# FT232RL.net
KiCad netlist of a schematic drawn in Altium Designer
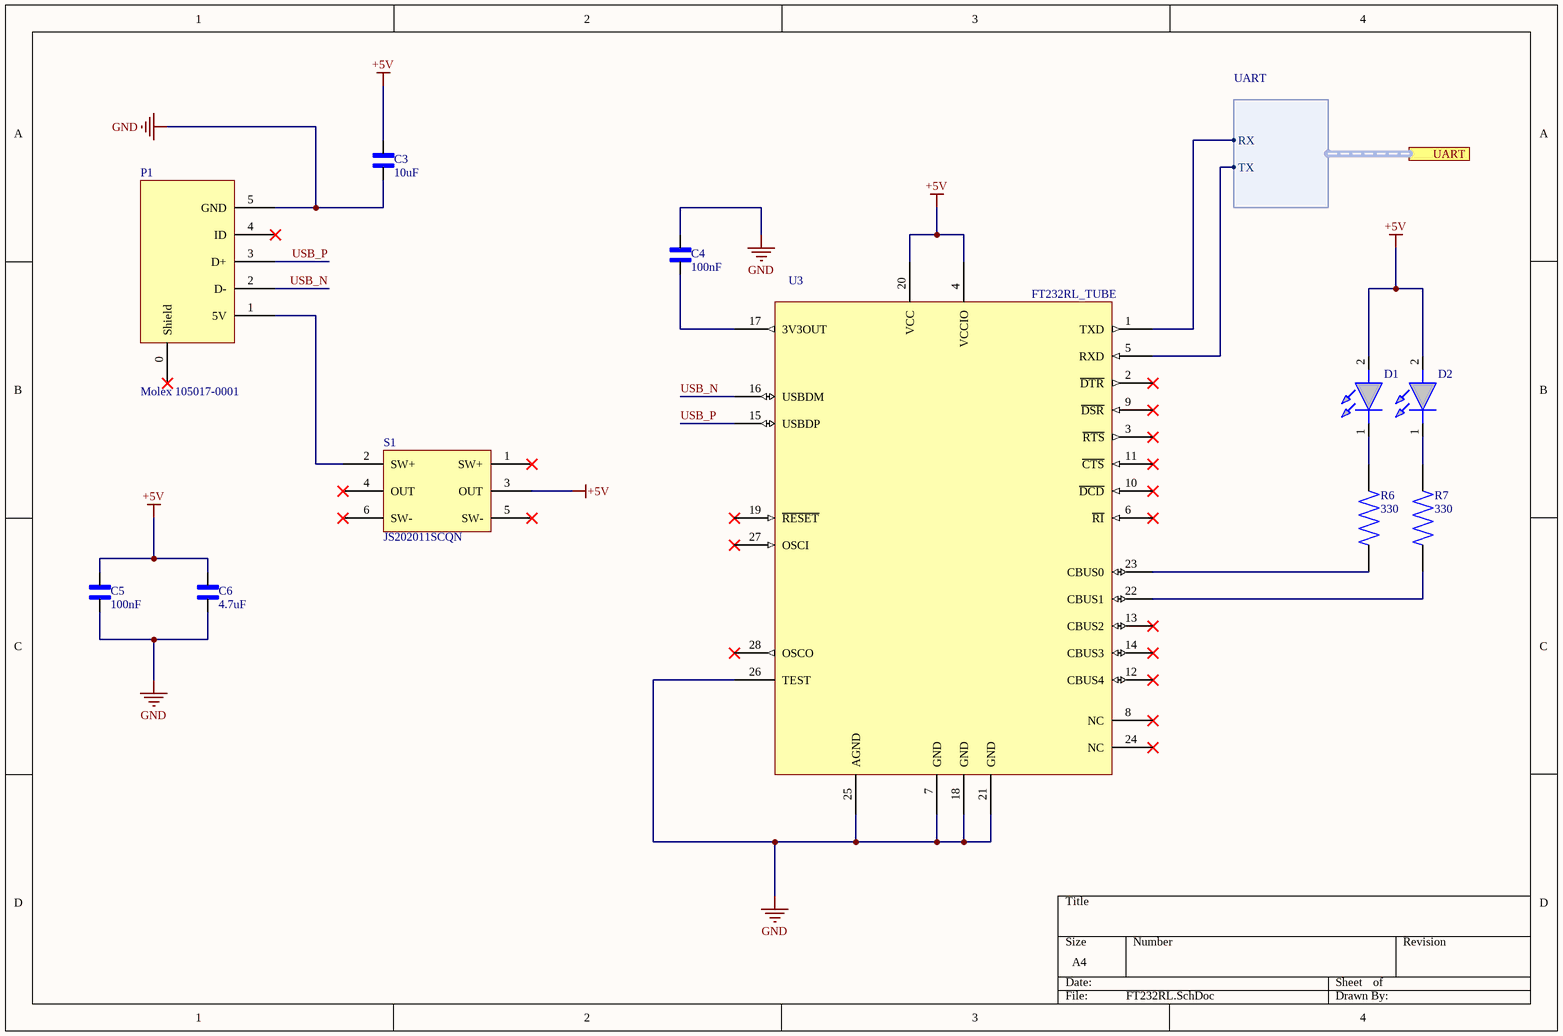
[diagram p0: FT232RL.SchDoc]

(export (version "E")
  (design (tool "Eeschema 10.0.6"))
  (components
    (comp (ref "C3")
      (value "10uF")
      (footprint "CAPC1608X90N")
      (fields (field (name "MF") "{'manufacturer': u'Murata'}") (field (name "MP") "GRM188R71C104KA01D"))
      (libsource (lib "GRM188R71C104KA01D") (part "GRM188R71C104KA01D"))
    )
    (comp (ref "C4")
      (value "100nF")
      (footprint "CAPC1608X90N")
      (fields (field (name "MF") "{'manufacturer': u'Murata'}") (field (name "MP") "GRM188R71C104KA01D"))
      (libsource (lib "GRM188R71C104KA01D") (part "GRM188R71C104KA01D"))
    )
    (comp (ref "C5")
      (value "100nF")
      (footprint "CAPC1608X90N")
      (fields (field (name "MF") "{'manufacturer': u'Murata'}") (field (name "MP") "GRM188R71C104KA01D"))
      (libsource (lib "GRM188R71C104KA01D") (part "GRM188R71C104KA01D"))
    )
    (comp (ref "C6")
      (value "4.7uF")
      (footprint "CAPC1608X90N")
      (fields (field (name "MF") "{'manufacturer': u'Murata'}") (field (name "MP") "GRM188R71C104KA01D"))
      (libsource (lib "GRM188R71C104KA01D") (part "GRM188R71C104KA01D"))
    )
    (comp (ref "D1")
      (value "VLMTG1300-GS08")
      (footprint "LEDC1608X100N")
      (description "Vishay VLMTG1300-GS08, 525 nm Green LED, 1608 (0603) SMD package")
      (libsource (lib "LED_VLMTG1300-GS08") (part "VLMTG1300-GS08"))
    )
    (comp (ref "D2")
      (value "VLMTG1300-GS08")
      (footprint "LEDC1608X100N")
      (description "Vishay VLMTG1300-GS08, 525 nm Green LED, 1608 (0603) SMD package")
      (libsource (lib "LED_VLMTG1300-GS08") (part "VLMTG1300-GS08"))
    )
    (comp (ref "P1")
      (value "Molex 105017-0001")
      (footprint "Molex 105017-0001")
      (description "CONN RCPT MICRO USB R/A SMD")
      (libsource (lib "Ala") (part "Molex 105017-0001"))
    )
    (comp (ref "R6")
      (value "330")
      (footprint "CRCW06032K20FKEA:RESC1508X50N")
      (fields (field (name "MF") "{'manufacturer': u'Vishay Dale'}") (field (name "MP") "CRCW06032K20FKEA"))
      (libsource (lib "CRCW06032K20FKEA") (part "CRCW06032K20FKEA"))
    )
    (comp (ref "R7")
      (value "330")
      (footprint "CRCW06032K20FKEA:RESC1508X50N")
      (fields (field (name "MF") "{'manufacturer': u'Vishay Dale'}") (field (name "MP") "CRCW06032K20FKEA"))
      (libsource (lib "CRCW06032K20FKEA") (part "CRCW06032K20FKEA"))
    )
    (comp (ref "S1")
      (value "JS202011SCQN")
      (footprint "SW_JS202011SCQN")
      (description "JS Series DPDT On-On Gull Wing Surface Mount Subminiature Slide Switch")
      (libsource (lib "Ala") (part "SW_JS202011SCQN"))
    )
    (comp (ref "U3")
      (value "FT232RL_TUBE")
      (footprint "FT232RL_TUBE")
      (description "FT232RL-Tube\r\nUSB UART Asynchronous Serial Data Transfer Chip, 28-pin SSOP, Tube")
      (libsource (lib "Ala") (part "FT232RL_TUBE"))
    )
  )
  (nets
    (net (code "2") (name "+5V") (class "Default")
      (node (ref "C3") (pin "2") (pinfunction "2_2") (pintype "passive"))
      (node (ref "C5") (pin "2") (pinfunction "2_2") (pintype "passive"))
      (node (ref "C6") (pin "2") (pinfunction "2_2") (pintype "passive"))
      (node (ref "D1") (pin "2") (pinfunction "A_2") (pintype "passive"))
      (node (ref "D2") (pin "2") (pinfunction "A_2") (pintype "passive"))
      (node (ref "S1") (pin "3") (pinfunction "OUT_3") (pintype "passive"))
      (node (ref "U3") (pin "20") (pinfunction "VCC_20") (pintype "passive"))
      (node (ref "U3") (pin "4") (pinfunction "VCCIO_4") (pintype "passive"))
    )
    (net (code "3") (name "/RX") (class "Default")
      (node (ref "U3") (pin "1") (pinfunction "TXD_1") (pintype "output"))
    )
    (net (code "4") (name "/TX") (class "Default")
      (node (ref "U3") (pin "5") (pinfunction "RXD_5") (pintype "input"))
    )
    (net (code "5") (name "/USB_N") (class "Default")
      (node (ref "P1") (pin "2") (pinfunction "D-_2") (pintype "passive"))
      (node (ref "U3") (pin "16") (pinfunction "USBDM_16") (pintype "bidirectional"))
    )
    (net (code "6") (name "/USB_P") (class "Default")
      (node (ref "P1") (pin "3") (pinfunction "D+_3") (pintype "passive"))
      (node (ref "U3") (pin "15") (pinfunction "USBDP_15") (pintype "bidirectional"))
    )
    (net (code "8") (name "GND") (class "Default")
      (node (ref "C3") (pin "1") (pinfunction "1_1") (pintype "passive"))
      (node (ref "C4") (pin "2") (pinfunction "2_2") (pintype "passive"))
      (node (ref "C5") (pin "1") (pinfunction "1_1") (pintype "passive"))
      (node (ref "C6") (pin "1") (pinfunction "1_1") (pintype "passive"))
      (node (ref "P1") (pin "5") (pinfunction "GND_5") (pintype "passive"))
      (node (ref "U3") (pin "18") (pinfunction "GND_18") (pintype "passive"))
      (node (ref "U3") (pin "21") (pinfunction "GND_21") (pintype "passive"))
      (node (ref "U3") (pin "25") (pinfunction "AGND_25") (pintype "passive"))
      (node (ref "U3") (pin "26") (pinfunction "TEST_26") (pintype "passive"))
      (node (ref "U3") (pin "7") (pinfunction "GND_7") (pintype "passive"))
    )
    (net (code "9") (name "Net-(D1-K)") (class "Default")
      (node (ref "D1") (pin "1") (pinfunction "K_1") (pintype "passive"))
      (node (ref "R6") (pin "2") (pinfunction "2_2") (pintype "passive"))
    )
    (net (code "10") (name "Net-(D2-K)") (class "Default")
      (node (ref "D2") (pin "1") (pinfunction "K_1") (pintype "passive"))
      (node (ref "R7") (pin "2") (pinfunction "2_2") (pintype "passive"))
    )
    (net (code "11") (name "Net-(P1-5V)") (class "Default")
      (node (ref "P1") (pin "1") (pinfunction "5V_1") (pintype "passive"))
      (node (ref "S1") (pin "2") (pinfunction "SW+_2") (pintype "passive"))
    )
    (net (code "12") (name "Net-(U3-3V3OUT)") (class "Default")
      (node (ref "C4") (pin "1") (pinfunction "1_1") (pintype "passive"))
      (node (ref "U3") (pin "17") (pinfunction "3V3OUT_17") (pintype "output"))
    )
    (net (code "13") (name "Net-(U3-CBUS0)") (class "Default")
      (node (ref "R6") (pin "1") (pinfunction "1_1") (pintype "passive"))
      (node (ref "U3") (pin "23") (pinfunction "CBUS0_23") (pintype "bidirectional"))
    )
    (net (code "14") (name "Net-(U3-CBUS1)") (class "Default")
      (node (ref "R7") (pin "1") (pinfunction "1_1") (pintype "passive"))
      (node (ref "U3") (pin "22") (pinfunction "CBUS1_22") (pintype "bidirectional"))
    )
    (net (code "15") (name "unconnected-(P1-ID-Pad4)") (class "Default")
      (node (ref "P1") (pin "4") (pinfunction "ID_4") (pintype "passive+no_connect"))
    )
    (net (code "16") (name "unconnected-(P1-Shield-Pad0)") (class "Default")
      (node (ref "P1") (pin "0") (pinfunction "Shield_0") (pintype "passive+no_connect"))
    )
    (net (code "17") (name "unconnected-(S1-OUT-Pad4)") (class "Default")
      (node (ref "S1") (pin "4") (pinfunction "OUT_4") (pintype "passive+no_connect"))
    )
    (net (code "18") (name "unconnected-(S1-SW+-Pad1)") (class "Default")
      (node (ref "S1") (pin "1") (pinfunction "SW+_1") (pintype "passive+no_connect"))
    )
    (net (code "19") (name "unconnected-(S1-SW--Pad5)") (class "Default")
      (node (ref "S1") (pin "5") (pinfunction "SW-_5") (pintype "passive+no_connect"))
    )
    (net (code "20") (name "unconnected-(S1-SW--Pad6)") (class "Default")
      (node (ref "S1") (pin "6") (pinfunction "SW-_6") (pintype "passive+no_connect"))
    )
    (net (code "21") (name "unconnected-(U3-CBUS2-Pad13)") (class "Default")
      (node (ref "U3") (pin "13") (pinfunction "CBUS2_13") (pintype "bidirectional+no_connect"))
    )
    (net (code "22") (name "unconnected-(U3-CBUS3-Pad14)") (class "Default")
      (node (ref "U3") (pin "14") (pinfunction "CBUS3_14") (pintype "bidirectional+no_connect"))
    )
    (net (code "23") (name "unconnected-(U3-CBUS4-Pad12)") (class "Default")
      (node (ref "U3") (pin "12") (pinfunction "CBUS4_12") (pintype "bidirectional+no_connect"))
    )
    (net (code "24") (name "unconnected-(U3-NC-Pad8)") (class "Default")
      (node (ref "U3") (pin "8") (pinfunction "NC_8") (pintype "passive+no_connect"))
    )
    (net (code "25") (name "unconnected-(U3-NC-Pad24)") (class "Default")
      (node (ref "U3") (pin "24") (pinfunction "NC_24") (pintype "passive+no_connect"))
    )
    (net (code "26") (name "unconnected-(U3-OSCI-Pad27)") (class "Default")
      (node (ref "U3") (pin "27") (pinfunction "OSCI_27") (pintype "input+no_connect"))
    )
    (net (code "27") (name "unconnected-(U3-OSCO-Pad28)") (class "Default")
      (node (ref "U3") (pin "28") (pinfunction "OSCO_28") (pintype "output+no_connect"))
    )
    (net (code "28") (name "unconnected-(U3-~{CTS}-Pad11)") (class "Default")
      (node (ref "U3") (pin "11") (pinfunction "~{CTS}_11") (pintype "input+no_connect"))
    )
    (net (code "29") (name "unconnected-(U3-~{DCD}-Pad10)") (class "Default")
      (node (ref "U3") (pin "10") (pinfunction "~{DCD}_10") (pintype "input+no_connect"))
    )
    (net (code "30") (name "unconnected-(U3-~{DSR}-Pad9)") (class "Default")
      (node (ref "U3") (pin "9") (pinfunction "~{DSR}_9") (pintype "input+no_connect"))
    )
    (net (code "31") (name "unconnected-(U3-~{DTR}-Pad2)") (class "Default")
      (node (ref "U3") (pin "2") (pinfunction "~{DTR}_2") (pintype "output+no_connect"))
    )
    (net (code "32") (name "unconnected-(U3-~{RESET}-Pad19)") (class "Default")
      (node (ref "U3") (pin "19") (pinfunction "~{RESET}_19") (pintype "input+no_connect"))
    )
    (net (code "33") (name "unconnected-(U3-~{RI}-Pad6)") (class "Default")
      (node (ref "U3") (pin "6") (pinfunction "~{RI}_6") (pintype "input+no_connect"))
    )
    (net (code "34") (name "unconnected-(U3-~{RTS}-Pad3)") (class "Default")
      (node (ref "U3") (pin "3") (pinfunction "~{RTS}_3") (pintype "output+no_connect"))
    )
  )
)
